# Rigid-QFN-1.net
KiCad netlist of a schematic drawn in Altium Designer
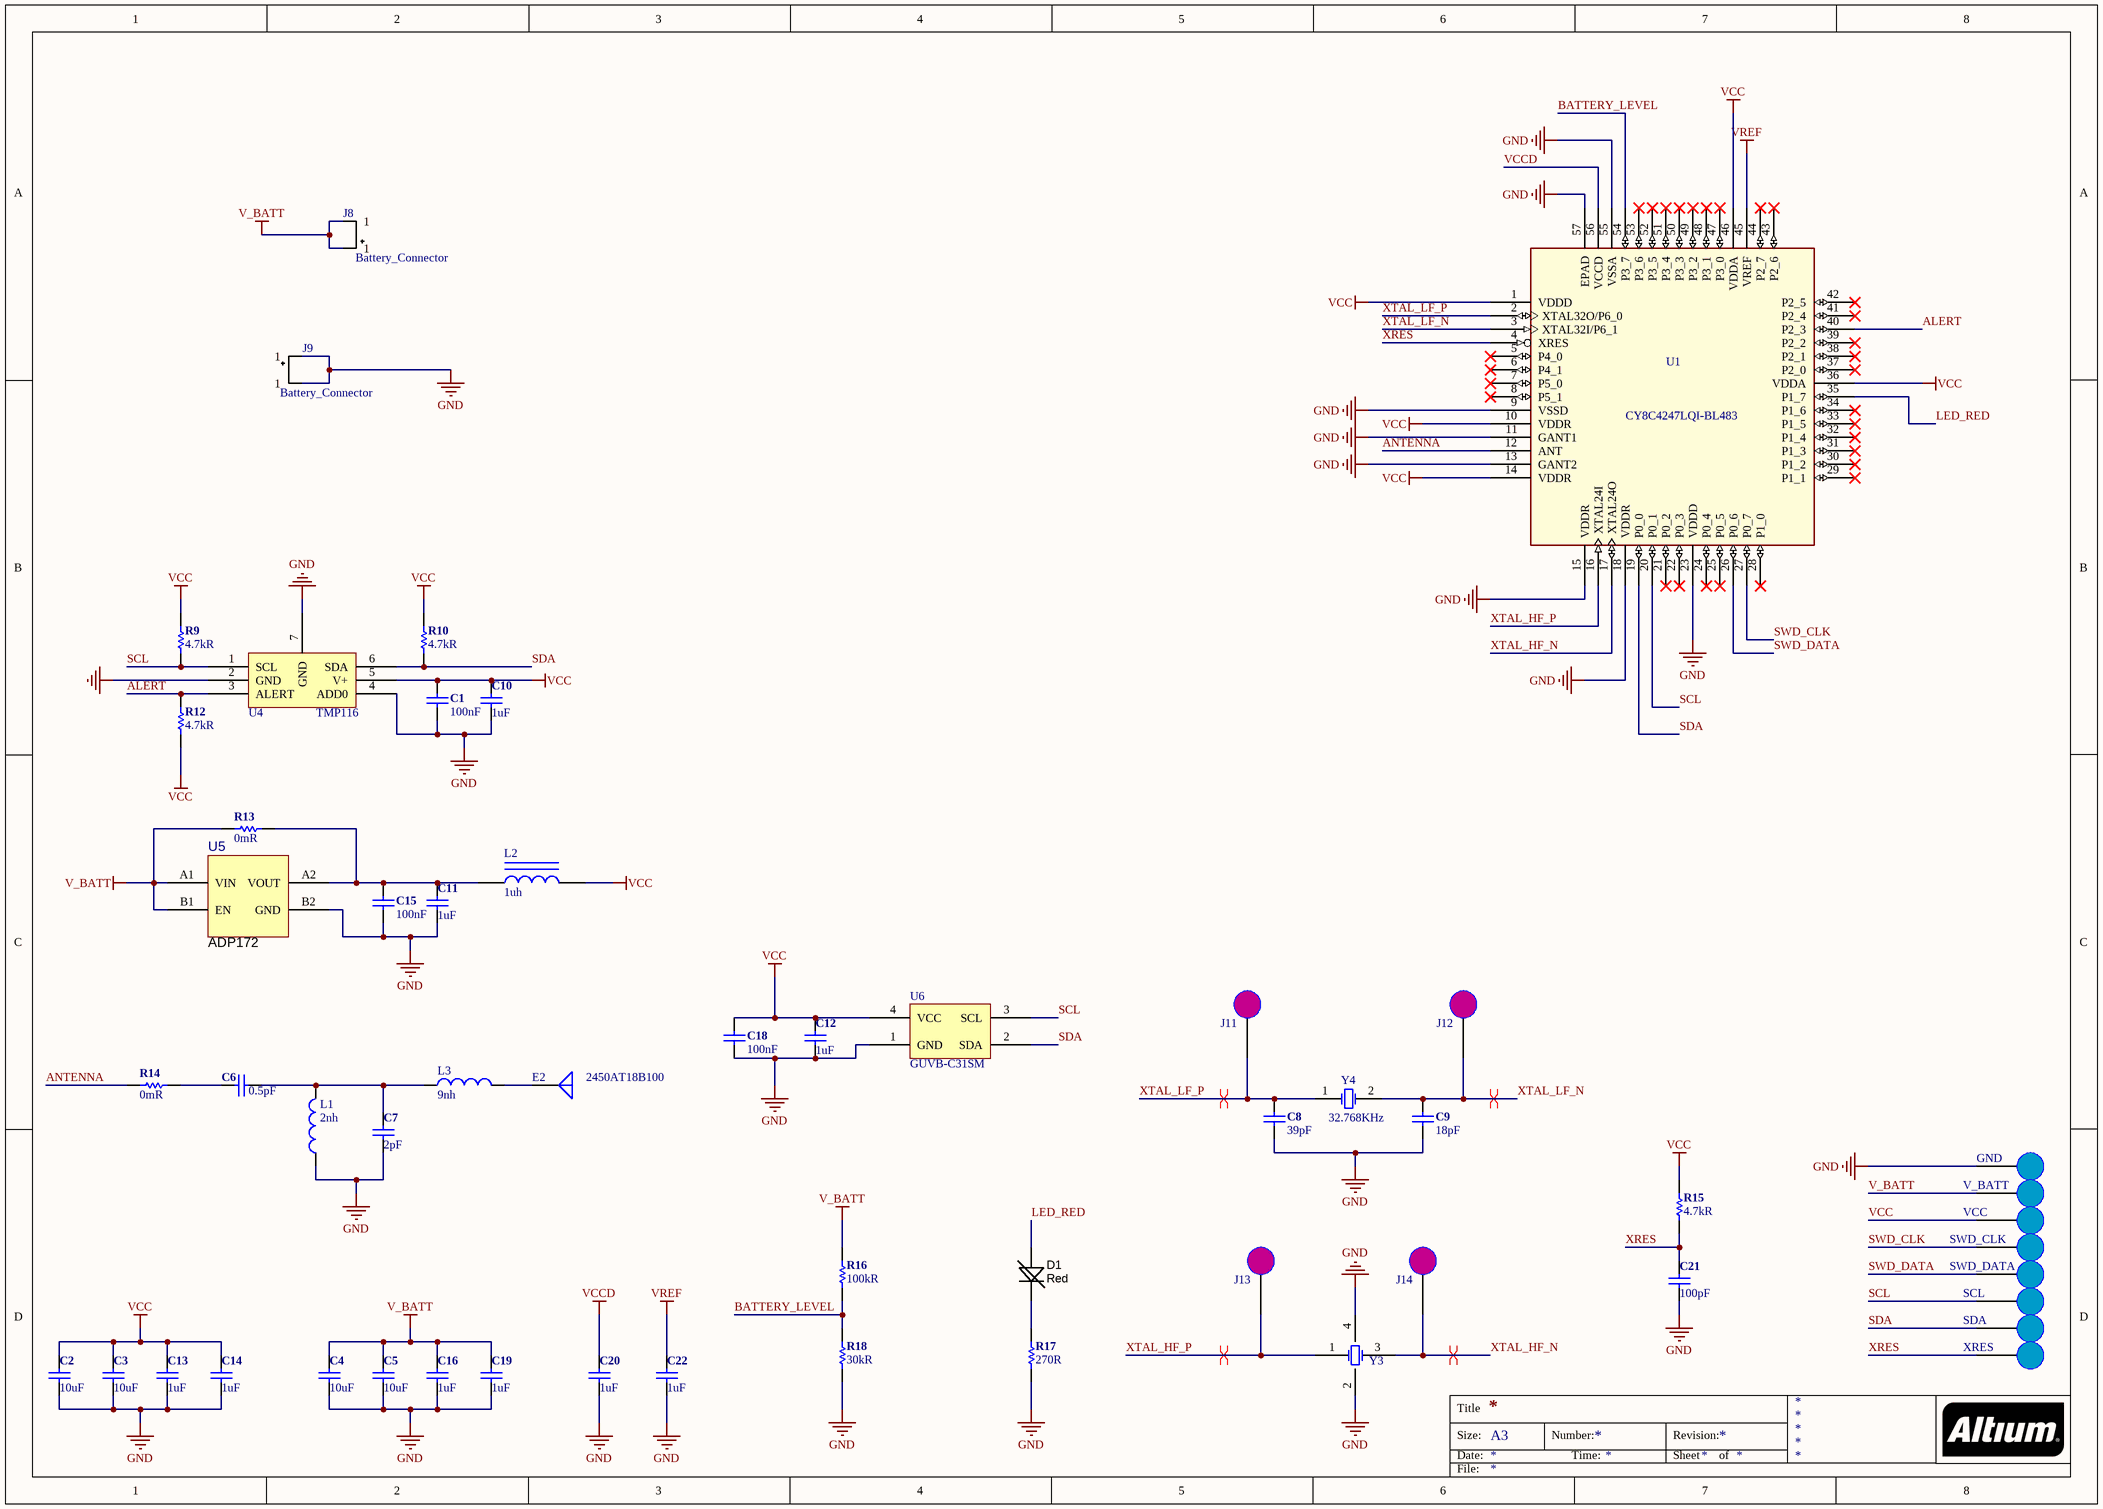
[diagram p0: Rigid-QFN-1.SchDoc]

(export (version "E")
  (design (tool "Eeschema 10.0.6"))
  (components
    (comp (ref "C1")
      (value "100nF")
      (footprint "CAP_0402(1005)_M")
      (description "___ OHM ___ mW 0402(1005) SMD")
      (fields
        (field (name "MANUFACTURER") "Yageo")
        (field (name "MANUFACTURER PART NUMBER") "CC0402ZRY5V6BB104")
      )
      (libsource (lib "tempsensor") (part "C-0402(1005)"))
    )
    (comp (ref "C2")
      (value "10uF")
      (footprint "CAP_0402(1005)_M")
      (description "___ OHM ___ mW 0402(1005) SMD")
      (fields
        (field (name "MANUFACTURER") "Murata")
        (field (name "MANUFACTURER PART NUMBER") "GRM155R60J106ME15D")
      )
      (libsource (lib "tempsensor") (part "C-0402(1005)"))
    )
    (comp (ref "C3")
      (value "10uF")
      (footprint "CAP_0402(1005)_M")
      (description "___ OHM ___ mW 0402(1005) SMD")
      (fields
        (field (name "MANUFACTURER") "Murata")
        (field (name "MANUFACTURER PART NUMBER") "GRM155R60J106ME15D")
      )
      (libsource (lib "tempsensor") (part "C-0402(1005)"))
    )
    (comp (ref "C4")
      (value "10uF")
      (footprint "CAP_0402(1005)_M")
      (description "___ OHM ___ mW 0402(1005) SMD")
      (fields
        (field (name "MANUFACTURER") "Murata")
        (field (name "MANUFACTURER PART NUMBER") "GRM155R60J106ME15D")
      )
      (libsource (lib "tempsensor") (part "C-0402(1005)"))
    )
    (comp (ref "C5")
      (value "10uF")
      (footprint "CAP_0402(1005)_M")
      (description "___ OHM ___ mW 0402(1005) SMD")
      (fields
        (field (name "MANUFACTURER") "Murata")
        (field (name "MANUFACTURER PART NUMBER") "GRM155R60J106ME15D")
      )
      (libsource (lib "tempsensor") (part "C-0402(1005)"))
    )
    (comp (ref "C6")
      (value "0.5pF")
      (footprint "CAP_0402(1005)_M")
      (description "___ OHM ___ mW 0402(1005) SMD")
      (fields
        (field (name "MANUFACTURER") "Murata")
        (field (name "MANUFACTURER PART NUMBER") "GJM1555C1HR50WB01D")
      )
      (libsource (lib "tempsensor") (part "C-0402(1005)"))
    )
    (comp (ref "C7")
      (value "2pF")
      (footprint "CAP_0402(1005)_M")
      (description "___ OHM ___ mW 0402(1005) SMD")
      (fields
        (field (name "MANUFACTURER") "Murata")
        (field (name "MANUFACTURER PART NUMBER") "GJM1555C1H2R0BB01D")
      )
      (libsource (lib "tempsensor") (part "C-0402(1005)"))
    )
    (comp (ref "C8")
      (value "39pF")
      (footprint "CAP_0402(1005)_M")
      (description "___ OHM ___ mW 0402(1005) SMD")
      (fields
        (field (name "MANUFACTURER") "KEMET")
        (field (name "MANUFACTURER PART NUMBER") "CBR04C390F5GAC")
      )
      (libsource (lib "tempsensor") (part "C-0402(1005)"))
    )
    (comp (ref "C9")
      (value "18pF")
      (footprint "CAP_0402(1005)_M")
      (description "___ OHM ___ mW 0402(1005) SMD")
      (fields
        (field (name "MANUFACTURER") "Murata")
        (field (name "MANUFACTURER PART NUMBER") "GJM1555C1H180FB01D")
      )
      (libsource (lib "tempsensor") (part "C-0402(1005)"))
    )
    (comp (ref "C10")
      (value "1uF")
      (footprint "CAP_0402(1005)_M")
      (description "___ OHM ___ mW 0402(1005) SMD")
      (fields
        (field (name "MANUFACTURER") "KEMET")
        (field (name "MANUFACTURER PART NUMBER") "C0402C105K8PACTU")
      )
      (libsource (lib "tempsensor") (part "C-0402(1005)"))
    )
    (comp (ref "C11")
      (value "1uF")
      (footprint "CAP_0402(1005)_M")
      (description "___ OHM ___ mW 0402(1005) SMD")
      (fields
        (field (name "MANUFACTURER") "KEMET")
        (field (name "MANUFACTURER PART NUMBER") "C0402C105K8PACTU")
      )
      (libsource (lib "tempsensor") (part "C-0402(1005)"))
    )
    (comp (ref "C12")
      (value "1uF")
      (footprint "CAP_0402(1005)_M")
      (description "___ OHM ___ mW 0402(1005) SMD")
      (fields
        (field (name "MANUFACTURER") "KEMET")
        (field (name "MANUFACTURER PART NUMBER") "C0402C105K8PACTU")
      )
      (libsource (lib "tempsensor") (part "C-0402(1005)"))
    )
    (comp (ref "C13")
      (value "1uF")
      (footprint "CAP_0402(1005)_M")
      (description "___ OHM ___ mW 0402(1005) SMD")
      (fields
        (field (name "MANUFACTURER") "KEMET")
        (field (name "MANUFACTURER PART NUMBER") "C0402C105K8PACTU")
      )
      (libsource (lib "tempsensor") (part "C-0402(1005)"))
    )
    (comp (ref "C14")
      (value "1uF")
      (footprint "CAP_0402(1005)_M")
      (description "___ OHM ___ mW 0402(1005) SMD")
      (fields
        (field (name "MANUFACTURER") "KEMET")
        (field (name "MANUFACTURER PART NUMBER") "C0402C105K8PACTU")
      )
      (libsource (lib "tempsensor") (part "C-0402(1005)"))
    )
    (comp (ref "C15")
      (value "100nF")
      (footprint "CAP_0402(1005)_M")
      (description "___ OHM ___ mW 0402(1005) SMD")
      (fields
        (field (name "MANUFACTURER") "Yageo")
        (field (name "MANUFACTURER PART NUMBER") "CC0402ZRY5V6BB104")
      )
      (libsource (lib "tempsensor") (part "C-0402(1005)"))
    )
    (comp (ref "C16")
      (value "1uF")
      (footprint "CAP_0402(1005)_M")
      (description "___ OHM ___ mW 0402(1005) SMD")
      (fields
        (field (name "MANUFACTURER") "KEMET")
        (field (name "MANUFACTURER PART NUMBER") "C0402C105K8PACTU")
      )
      (libsource (lib "tempsensor") (part "C-0402(1005)"))
    )
    (comp (ref "C18")
      (value "100nF")
      (footprint "CAP_0402(1005)_M")
      (description "___ OHM ___ mW 0402(1005) SMD")
      (fields
        (field (name "MANUFACTURER") "Yageo")
        (field (name "MANUFACTURER PART NUMBER") "CC0402ZRY5V6BB104")
      )
      (libsource (lib "tempsensor") (part "C-0402(1005)"))
    )
    (comp (ref "C19")
      (value "1uF")
      (footprint "CAP_0402(1005)_M")
      (description "___ OHM ___ mW 0402(1005) SMD")
      (fields
        (field (name "MANUFACTURER") "KEMET")
        (field (name "MANUFACTURER PART NUMBER") "C0402C105K8PACTU")
      )
      (libsource (lib "tempsensor") (part "C-0402(1005)"))
    )
    (comp (ref "C20")
      (value "1uF")
      (footprint "CAP_0402(1005)_M")
      (description "___ OHM ___ mW 0402(1005) SMD")
      (fields
        (field (name "MANUFACTURER") "KEMET")
        (field (name "MANUFACTURER PART NUMBER") "C0402C105K8PACTU")
      )
      (libsource (lib "tempsensor") (part "C-0402(1005)"))
    )
    (comp (ref "C21")
      (value "100pF")
      (footprint "CAP_0402(1005)_M")
      (description "___ OHM ___ mW 0402(1005) SMD")
      (fields
        (field (name "MANUFACTURER") "Wurth Electronics")
        (field (name "MANUFACTURER PART NUMBER") "885012005013")
      )
      (libsource (lib "tempsensor") (part "C-0402(1005)"))
    )
    (comp (ref "C22")
      (value "1uF")
      (footprint "CAP_0402(1005)_M")
      (description "___ OHM ___ mW 0402(1005) SMD")
      (fields
        (field (name "MANUFACTURER") "KEMET")
        (field (name "MANUFACTURER PART NUMBER") "C0402C105K8PACTU")
      )
      (libsource (lib "tempsensor") (part "C-0402(1005)"))
    )
    (comp (ref "D1")
      (value "Red")
      (footprint "LED_0402(1005)")
      (description "LED, 0402(1005) SMD")
      (fields
        (field (name "MANUFACTURER") "Kingbright")
        (field (name "MANUFACTURER PART NUMBER") "APHHS1005SURCK")
      )
      (libsource (lib "tempsensor") (part "LED_0402(1005)"))
    )
    (comp (ref "E2")
      (value "2450AT18B100")
      (footprint "2450AT18B100")
      (description "2.4 GHz BLE Antenna")
      (fields
        (field (name "MANUFACTURER") "Johanson")
        (field (name "MANUFACTURER PART NUMBER") "2450AT18B100E")
      )
      (libsource (lib "tempsensor") (part "2450AT18B100"))
    )
    (comp (ref "GND")
      (value "Probe-Pin Pad")
      (footprint "Pogo-Pin-Pad")
      (libsource (lib "tempsensor") (part "Probe-Pin Pad"))
    )
    (comp (ref "J8")
      (value "Battery_Connector")
      (footprint "Battery_PAD")
      (libsource (lib "tempsensor") (part "Battery_Connector"))
    )
    (comp (ref "J9")
      (value "Battery_Connector")
      (footprint "Battery_PAD")
      (libsource (lib "tempsensor") (part "Battery_Connector"))
    )
    (comp (ref "J11")
      (value "Probe-CLOCK")
      (footprint "Pogo-CLOCK-PAD")
      (libsource (lib "tempsensor") (part "Probe-CLOCK"))
    )
    (comp (ref "J12")
      (value "Probe-CLOCK")
      (footprint "Pogo-CLOCK-PAD")
      (libsource (lib "tempsensor") (part "Probe-CLOCK"))
    )
    (comp (ref "J13")
      (value "Probe-CLOCK")
      (footprint "Pogo-CLOCK-PAD")
      (libsource (lib "tempsensor") (part "Probe-CLOCK"))
    )
    (comp (ref "J14")
      (value "Probe-CLOCK")
      (footprint "Pogo-CLOCK-PAD")
      (libsource (lib "tempsensor") (part "Probe-CLOCK"))
    )
    (comp (ref "L1")
      (value "2nh")
      (footprint "IND_0402(1005)_M")
      (fields
        (field (name "MANUFACTURER") "Abracon")
        (field (name "MANUFACTURER PART NUMBER") "AISC-0402-2N0J-T")
        (field (name "TOLERANCE") "5%")
      )
      (libsource (lib "tempsensor") (part "I-0402(1005)"))
    )
    (comp (ref "L2")
      (value "1uh")
      (footprint "IND_0402(1005)_M")
      (description "Magnetic-Core Inductor")
      (fields
        (field (name "MANUFACTURER") "TDK")
        (field (name "MANUFACTURER PART NUMBER") "MLZ1005M1R0WT000")
      )
      (libsource (lib "tempsensor") (part "Inductor Iron"))
    )
    (comp (ref "L3")
      (value "9nh")
      (footprint "IND_0402(1005)_M")
      (fields
        (field (name "MANUFACTURER") "Murata")
        (field (name "MANUFACTURER PART NUMBER") "LQW15AN9N0G80D")
        (field (name "TOLERANCE") "2%")
      )
      (libsource (lib "tempsensor") (part "I-0402(1005)"))
    )
    (comp (ref "R9")
      (value "4.7kR")
      (footprint "RES_0402(1005)_M")
      (description "___ OHM ___ mW 0402(1005) SMD")
      (fields
        (field (name "MANUFACTURER") "Yageo")
        (field (name "MANUFACTURER PART NUMBER") "RC0402JR-074K7P")
      )
      (libsource (lib "tempsensor") (part "R-0402(1005)"))
    )
    (comp (ref "R10")
      (value "4.7kR")
      (footprint "RES_0402(1005)_M")
      (description "___ OHM ___ mW 0402(1005) SMD")
      (fields
        (field (name "MANUFACTURER") "Yageo")
        (field (name "MANUFACTURER PART NUMBER") "RC0402JR-074K7P")
      )
      (libsource (lib "tempsensor") (part "R-0402(1005)"))
    )
    (comp (ref "R12")
      (value "4.7kR")
      (footprint "RES_0402(1005)_M")
      (description "___ OHM ___ mW 0402(1005) SMD")
      (fields
        (field (name "MANUFACTURER") "Yageo")
        (field (name "MANUFACTURER PART NUMBER") "RC0402JR-074K7P")
      )
      (libsource (lib "tempsensor") (part "R-0402(1005)"))
    )
    (comp (ref "R13")
      (value "0mR")
      (footprint "RES_0402(1005)_M")
      (description "___ OHM ___ mW 0402(1005) SMD")
      (fields
        (field (name "MANUFACTURER") "Yageo")
        (field (name "MANUFACTURER PART NUMBER") "AC0402JR-070RL")
      )
      (libsource (lib "tempsensor") (part "R-0402(1005)"))
    )
    (comp (ref "R14")
      (value "0mR")
      (footprint "RES_0402(1005)_M")
      (description "___ OHM ___ mW 0402(1005) SMD")
      (fields
        (field (name "MANUFACTURER") "Yageo")
        (field (name "MANUFACTURER PART NUMBER") "AC0402JR-070RL")
      )
      (libsource (lib "tempsensor") (part "R-0402(1005)"))
    )
    (comp (ref "R15")
      (value "4.7kR")
      (footprint "RES_0402(1005)_M")
      (description "___ OHM ___ mW 0402(1005) SMD")
      (fields
        (field (name "MANUFACTURER") "Yageo")
        (field (name "MANUFACTURER PART NUMBER") "RC0402JR-074K7P")
      )
      (libsource (lib "tempsensor") (part "R-0402(1005)"))
    )
    (comp (ref "R16")
      (value "100kR")
      (footprint "RES_0402(1005)_M")
      (description "___ OHM ___ mW 0402(1005) SMD")
      (fields
        (field (name "MANUFACTURER") "Yageo")
        (field (name "MANUFACTURER PART NUMBER") "AC0402JR-07100KL")
      )
      (libsource (lib "tempsensor") (part "R-0402(1005)"))
    )
    (comp (ref "R17")
      (value "270R")
      (footprint "RES_0402(1005)_M")
      (description "___ OHM ___ mW 0402(1005) SMD")
      (fields
        (field (name "MANUFACTURER") "Yageo")
        (field (name "MANUFACTURER PART NUMBER") "RC0402JR-07270RL")
      )
      (libsource (lib "tempsensor") (part "R-0402(1005)"))
    )
    (comp (ref "R18")
      (value "30kR")
      (footprint "RES_0402(1005)_M")
      (description "___ OHM ___ mW 0402(1005) SMD")
      (fields
        (field (name "MANUFACTURER") "Yageo")
        (field (name "MANUFACTURER PART NUMBER") "RC0402JR-0730KL")
      )
      (libsource (lib "tempsensor") (part "R-0402(1005)"))
    )
    (comp (ref "SCL")
      (value "Probe-Pin Pad")
      (footprint "Pogo-Pin-Pad")
      (libsource (lib "tempsensor") (part "Probe-Pin Pad"))
    )
    (comp (ref "SDA")
      (value "Probe-Pin Pad")
      (footprint "Pogo-Pin-Pad")
      (libsource (lib "tempsensor") (part "Probe-Pin Pad"))
    )
    (comp (ref "SWD_CLK")
      (value "Probe-Pin Pad")
      (footprint "Pogo-Pin-Pad")
      (libsource (lib "tempsensor") (part "Probe-Pin Pad"))
    )
    (comp (ref "SWD_DATA")
      (value "Probe-Pin Pad")
      (footprint "Pogo-Pin-Pad")
      (libsource (lib "tempsensor") (part "Probe-Pin Pad"))
    )
    (comp (ref "U1")
      (value "CY8C4247LQI-BL483")
      (footprint "QFN40P700X700X60-57N")
      (fields (field (name "MANUFACTURER") "Cypress"))
      (libsource (lib "tempsensor") (part "CY8C4247LQI-BL483"))
    )
    (comp (ref "U4")
      (value "TMP116")
      (footprint "WSON-6")
      (description "TI Digital I2C Temperature Sensor")
      (fields
        (field (name "MANUFACTURER") "Texas Instruments")
        (field (name "MANUFACTURER PART NUMBER") "TMP116AIDRVT")
      )
      (libsource (lib "tempsensor") (part "TMP116"))
    )
    (comp (ref "U5")
      (value "ADP172")
      (footprint "ADP172")
      (description "3V LDO")
      (fields
        (field (name "MANUFACTURER") "Analog Devices")
        (field (name "MANUFACTURER PART NUMBER") "ADP172ACBZ-3.0-R7")
      )
      (libsource (lib "tempsensor") (part "ADP172"))
    )
    (comp (ref "U6")
      (value "GUVB-C31SM")
      (footprint "GUVB-C31SM")
      (libsource (lib "tempsensor") (part "GUVB-C31SM"))
    )
    (comp (ref "VCC")
      (value "Probe-Pin Pad")
      (footprint "Pogo-Pin-Pad")
      (libsource (lib "tempsensor") (part "Probe-Pin Pad"))
    )
    (comp (ref "V_BATT")
      (value "Probe-Pin Pad")
      (footprint "Pogo-Pin-Pad")
      (libsource (lib "tempsensor") (part "Probe-Pin Pad"))
    )
    (comp (ref "XRES")
      (value "Probe-Pin Pad")
      (footprint "Pogo-Pin-Pad")
      (libsource (lib "tempsensor") (part "Probe-Pin Pad"))
    )
    (comp (ref "Y3")
      (value "ECX-2236")
      (footprint "ECX-2236")
      (description "24 MHz Crystal")
      (fields
        (field (name "MANUFACTURER") "ECS International")
        (field (name "MANUFACTURER PART NUMBER") "ECS-240-8-36CKM-TR")
      )
      (libsource (lib "tempsensor") (part "ECX-2236"))
    )
    (comp (ref "Y4")
      (value "32.768KHz")
      (footprint "ABS05")
      (description "Crystal Oscillator")
      (fields
        (field (name "MANUFACTURER") "Abracon")
        (field (name "MANUFACTURER PART NUMBER") "ABS05-32.768KHZ-T")
      )
      (libsource (lib "tempsensor") (part "ABS05"))
    )
  )
  (nets
    (net (code "1") (name "/ALERT") (class "Default")
      (node (ref "R12") (pin "2") (pinfunction "2_2") (pintype "passive"))
      (node (ref "U1") (pin "40") (pinfunction "P2_3_40") (pintype "bidirectional"))
      (node (ref "U4") (pin "3") (pinfunction "ALERT_3") (pintype "passive"))
    )
    (net (code "2") (name "/ANTENNA") (class "Default")
      (node (ref "R14") (pin "1") (pinfunction "1_1") (pintype "passive"))
      (node (ref "U1") (pin "12") (pinfunction "ANT_12") (pintype "passive"))
    )
    (net (code "3") (name "/BATTERY_LEVEL") (class "Default")
      (node (ref "R16") (pin "2") (pinfunction "2_2") (pintype "passive"))
      (node (ref "R18") (pin "1") (pinfunction "1_1") (pintype "passive"))
      (node (ref "U1") (pin "54") (pinfunction "P3_7_54") (pintype "bidirectional"))
    )
    (net (code "4") (name "/LED_RED") (class "Default")
      (node (ref "D1") (pin "A") (pinfunction "A_A") (pintype "passive"))
      (node (ref "U1") (pin "35") (pinfunction "P1_7_35") (pintype "bidirectional"))
    )
    (net (code "5") (name "/SCL") (class "Default")
      (node (ref "R9") (pin "1") (pinfunction "1_1") (pintype "passive"))
      (node (ref "SCL") (pin "1") (pinfunction "1_1") (pintype "passive"))
      (node (ref "U1") (pin "20") (pinfunction "P0_1_20") (pintype "bidirectional"))
      (node (ref "U4") (pin "1") (pinfunction "SCL_1") (pintype "passive"))
      (node (ref "U6") (pin "3") (pinfunction "SCL_3") (pintype "passive"))
    )
    (net (code "6") (name "/SDA") (class "Default")
      (node (ref "R10") (pin "1") (pinfunction "1_1") (pintype "passive"))
      (node (ref "SDA") (pin "1") (pinfunction "1_1") (pintype "passive"))
      (node (ref "U1") (pin "19") (pinfunction "P0_0_19") (pintype "bidirectional"))
      (node (ref "U4") (pin "6") (pinfunction "SDA_6") (pintype "passive"))
      (node (ref "U6") (pin "2") (pinfunction "SDA_2") (pintype "passive"))
    )
    (net (code "7") (name "/SWD_CLK") (class "Default")
      (node (ref "SWD_CLK") (pin "1") (pinfunction "1_1") (pintype "passive"))
      (node (ref "U1") (pin "27") (pinfunction "P0_7_27") (pintype "bidirectional"))
    )
    (net (code "8") (name "/SWD_DATA") (class "Default")
      (node (ref "SWD_DATA") (pin "1") (pinfunction "1_1") (pintype "passive"))
      (node (ref "U1") (pin "26") (pinfunction "P0_6_26") (pintype "bidirectional"))
    )
    (net (code "9") (name "/XRES") (class "Default")
      (node (ref "C21") (pin "1") (pinfunction "1_1") (pintype "passive"))
      (node (ref "R15") (pin "2") (pinfunction "2_2") (pintype "passive"))
      (node (ref "U1") (pin "4") (pinfunction "XRES_4") (pintype "input"))
      (node (ref "XRES") (pin "1") (pinfunction "1_1") (pintype "passive"))
    )
    (net (code "10") (name "/XTAL_HF_N") (class "Default")
      (node (ref "J14") (pin "1") (pinfunction "1_1") (pintype "passive"))
      (node (ref "U1") (pin "17") (pinfunction "XTAL24O_17") (pintype "bidirectional"))
      (node (ref "Y3") (pin "3") (pinfunction "OSC2_3") (pintype "passive"))
    )
    (net (code "11") (name "/XTAL_HF_P") (class "Default")
      (node (ref "J13") (pin "1") (pinfunction "1_1") (pintype "passive"))
      (node (ref "U1") (pin "16") (pinfunction "XTAL24I_16") (pintype "input"))
      (node (ref "Y3") (pin "1") (pinfunction "OSC1_1") (pintype "passive"))
    )
    (net (code "12") (name "/XTAL_LF_N") (class "Default")
      (node (ref "C9") (pin "1") (pinfunction "1_1") (pintype "passive"))
      (node (ref "J12") (pin "1") (pinfunction "1_1") (pintype "passive"))
      (node (ref "U1") (pin "3") (pinfunction "XTAL32I/P6_1_3") (pintype "input"))
      (node (ref "Y4") (pin "2") (pinfunction "OSC2_2") (pintype "passive"))
    )
    (net (code "13") (name "/XTAL_LF_P") (class "Default")
      (node (ref "C8") (pin "1") (pinfunction "1_1") (pintype "passive"))
      (node (ref "J11") (pin "1") (pinfunction "1_1") (pintype "passive"))
      (node (ref "U1") (pin "2") (pinfunction "XTAL32O/P6_0_2") (pintype "bidirectional"))
      (node (ref "Y4") (pin "1") (pinfunction "OSC1_1") (pintype "passive"))
    )
    (net (code "14") (name "GND") (class "Default")
      (node (ref "C1") (pin "2") (pinfunction "2_2") (pintype "passive"))
      (node (ref "C10") (pin "2") (pinfunction "2_2") (pintype "passive"))
      (node (ref "C11") (pin "2") (pinfunction "2_2") (pintype "passive"))
      (node (ref "C12") (pin "2") (pinfunction "2_2") (pintype "passive"))
      (node (ref "C13") (pin "2") (pinfunction "2_2") (pintype "passive"))
      (node (ref "C14") (pin "2") (pinfunction "2_2") (pintype "passive"))
      (node (ref "C15") (pin "2") (pinfunction "2_2") (pintype "passive"))
      (node (ref "C16") (pin "2") (pinfunction "2_2") (pintype "passive"))
      (node (ref "C18") (pin "2") (pinfunction "2_2") (pintype "passive"))
      (node (ref "C19") (pin "2") (pinfunction "2_2") (pintype "passive"))
      (node (ref "C2") (pin "2") (pinfunction "2_2") (pintype "passive"))
      (node (ref "C20") (pin "2") (pinfunction "2_2") (pintype "passive"))
      (node (ref "C21") (pin "2") (pinfunction "2_2") (pintype "passive"))
      (node (ref "C22") (pin "2") (pinfunction "2_2") (pintype "passive"))
      (node (ref "C3") (pin "2") (pinfunction "2_2") (pintype "passive"))
      (node (ref "C4") (pin "2") (pinfunction "2_2") (pintype "passive"))
      (node (ref "C5") (pin "2") (pinfunction "2_2") (pintype "passive"))
      (node (ref "C7") (pin "2") (pinfunction "2_2") (pintype "passive"))
      (node (ref "C8") (pin "2") (pinfunction "2_2") (pintype "passive"))
      (node (ref "C9") (pin "2") (pinfunction "2_2") (pintype "passive"))
      (node (ref "GND") (pin "1") (pinfunction "1_1") (pintype "passive"))
      (node (ref "J9") (pin "1") (pinfunction "1_1") (pintype "passive"))
      (node (ref "L1") (pin "1") (pinfunction "1_1") (pintype "passive"))
      (node (ref "R17") (pin "2") (pinfunction "2_2") (pintype "passive"))
      (node (ref "R18") (pin "2") (pinfunction "2_2") (pintype "passive"))
      (node (ref "U1") (pin "11") (pinfunction "GANT1_11") (pintype "power_in"))
      (node (ref "U1") (pin "13") (pinfunction "GANT2_13") (pintype "power_in"))
      (node (ref "U1") (pin "15") (pinfunction "VDDR_15") (pintype "power_in"))
      (node (ref "U1") (pin "18") (pinfunction "VDDR_18") (pintype "power_in"))
      (node (ref "U1") (pin "23") (pinfunction "VDDD_23") (pintype "power_in"))
      (node (ref "U1") (pin "55") (pinfunction "VSSA_55") (pintype "power_in"))
      (node (ref "U1") (pin "57") (pinfunction "EPAD_57") (pintype "power_in"))
      (node (ref "U1") (pin "9") (pinfunction "VSSD_9") (pintype "power_in"))
      (node (ref "U4") (pin "2") (pinfunction "GND_2") (pintype "passive"))
      (node (ref "U4") (pin "4") (pinfunction "ADD0_4") (pintype "passive"))
      (node (ref "U4") (pin "7") (pinfunction "GND_7") (pintype "passive"))
      (node (ref "U5") (pin "B2") (pinfunction "GND_B2") (pintype "passive"))
      (node (ref "U6") (pin "1") (pinfunction "GND_1") (pintype "passive"))
      (node (ref "Y3") (pin "2") (pinfunction "GND_2") (pintype "passive"))
      (node (ref "Y3") (pin "4") (pinfunction "GND_4") (pintype "passive"))
    )
    (net (code "15") (name "Net-(C6-Pad1)") (class "Default")
      (node (ref "C6") (pin "1") (pinfunction "1_1") (pintype "passive"))
      (node (ref "R14") (pin "2") (pinfunction "2_2") (pintype "passive"))
    )
    (net (code "16") (name "Net-(C6-Pad2)") (class "Default")
      (node (ref "C6") (pin "2") (pinfunction "2_2") (pintype "passive"))
      (node (ref "C7") (pin "1") (pinfunction "1_1") (pintype "passive"))
      (node (ref "L1") (pin "2") (pinfunction "2_2") (pintype "passive"))
      (node (ref "L3") (pin "1") (pinfunction "1_1") (pintype "passive"))
    )
    (net (code "17") (name "Net-(D1-PadK)") (class "Default")
      (node (ref "D1") (pin "K") (pinfunction "K_K") (pintype "passive"))
      (node (ref "R17") (pin "1") (pinfunction "1_1") (pintype "passive"))
    )
    (net (code "18") (name "Net-(E2-A)") (class "Default")
      (node (ref "E2") (pin "1") (pinfunction "A_1") (pintype "passive"))
      (node (ref "L3") (pin "2") (pinfunction "2_2") (pintype "passive"))
    )
    (net (code "19") (name "Net-(U5-VOUT)") (class "Default")
      (node (ref "C11") (pin "1") (pinfunction "1_1") (pintype "passive"))
      (node (ref "C15") (pin "1") (pinfunction "1_1") (pintype "passive"))
      (node (ref "L2") (pin "1") (pinfunction "1_1") (pintype "passive"))
      (node (ref "R13") (pin "2") (pinfunction "2_2") (pintype "passive"))
      (node (ref "U5") (pin "A2") (pinfunction "VOUT_A2") (pintype "passive"))
    )
    (net (code "20") (name "VCC") (class "Default")
      (node (ref "C1") (pin "1") (pinfunction "1_1") (pintype "passive"))
      (node (ref "C10") (pin "1") (pinfunction "1_1") (pintype "passive"))
      (node (ref "C12") (pin "1") (pinfunction "1_1") (pintype "passive"))
      (node (ref "C13") (pin "1") (pinfunction "1_1") (pintype "passive"))
      (node (ref "C14") (pin "1") (pinfunction "1_1") (pintype "passive"))
      (node (ref "C18") (pin "1") (pinfunction "1_1") (pintype "passive"))
      (node (ref "C2") (pin "1") (pinfunction "1_1") (pintype "passive"))
      (node (ref "C3") (pin "1") (pinfunction "1_1") (pintype "passive"))
      (node (ref "L2") (pin "2") (pinfunction "2_2") (pintype "passive"))
      (node (ref "R10") (pin "2") (pinfunction "2_2") (pintype "passive"))
      (node (ref "R12") (pin "1") (pinfunction "1_1") (pintype "passive"))
      (node (ref "R15") (pin "1") (pinfunction "1_1") (pintype "passive"))
      (node (ref "R9") (pin "2") (pinfunction "2_2") (pintype "passive"))
      (node (ref "U1") (pin "1") (pinfunction "VDDD_1") (pintype "power_in"))
      (node (ref "U1") (pin "10") (pinfunction "VDDR_10") (pintype "power_in"))
      (node (ref "U1") (pin "14") (pinfunction "VDDR_14") (pintype "power_in"))
      (node (ref "U1") (pin "36") (pinfunction "VDDA_36") (pintype "power_in"))
      (node (ref "U1") (pin "46") (pinfunction "VDDA_46") (pintype "power_in"))
      (node (ref "U4") (pin "5") (pinfunction "V+_5") (pintype "passive"))
      (node (ref "U6") (pin "4") (pinfunction "VCC_4") (pintype "passive"))
      (node (ref "VCC") (pin "1") (pinfunction "1_1") (pintype "passive"))
    )
    (net (code "21") (name "VCCD") (class "Default")
      (node (ref "C20") (pin "1") (pinfunction "1_1") (pintype "passive"))
      (node (ref "U1") (pin "56") (pinfunction "VCCD_56") (pintype "power_in"))
    )
    (net (code "22") (name "VREF") (class "Default")
      (node (ref "C22") (pin "1") (pinfunction "1_1") (pintype "passive"))
      (node (ref "U1") (pin "45") (pinfunction "VREF_45") (pintype "power_in"))
    )
    (net (code "23") (name "V_BATT") (class "Default")
      (node (ref "C16") (pin "1") (pinfunction "1_1") (pintype "passive"))
      (node (ref "C19") (pin "1") (pinfunction "1_1") (pintype "passive"))
      (node (ref "C4") (pin "1") (pinfunction "1_1") (pintype "passive"))
      (node (ref "C5") (pin "1") (pinfunction "1_1") (pintype "passive"))
      (node (ref "J8") (pin "1") (pinfunction "1_1") (pintype "passive"))
      (node (ref "R13") (pin "1") (pinfunction "1_1") (pintype "passive"))
      (node (ref "R16") (pin "1") (pinfunction "1_1") (pintype "passive"))
      (node (ref "U5") (pin "A1") (pinfunction "VIN_A1") (pintype "passive"))
      (node (ref "U5") (pin "B1") (pinfunction "EN_B1") (pintype "passive"))
      (node (ref "V_BATT") (pin "1") (pinfunction "1_1") (pintype "passive"))
    )
    (net (code "24") (name "unconnected-(U1-P0_2-Pad21)") (class "Default")
      (node (ref "U1") (pin "21") (pinfunction "P0_2_21") (pintype "bidirectional+no_connect"))
    )
    (net (code "25") (name "unconnected-(U1-P0_3-Pad22)") (class "Default")
      (node (ref "U1") (pin "22") (pinfunction "P0_3_22") (pintype "bidirectional+no_connect"))
    )
    (net (code "26") (name "unconnected-(U1-P0_4-Pad24)") (class "Default")
      (node (ref "U1") (pin "24") (pinfunction "P0_4_24") (pintype "bidirectional+no_connect"))
    )
    (net (code "27") (name "unconnected-(U1-P0_5-Pad25)") (class "Default")
      (node (ref "U1") (pin "25") (pinfunction "P0_5_25") (pintype "bidirectional+no_connect"))
    )
    (net (code "28") (name "unconnected-(U1-P1_0-Pad28)") (class "Default")
      (node (ref "U1") (pin "28") (pinfunction "P1_0_28") (pintype "bidirectional+no_connect"))
    )
    (net (code "29") (name "unconnected-(U1-P1_1-Pad29)") (class "Default")
      (node (ref "U1") (pin "29") (pinfunction "P1_1_29") (pintype "bidirectional+no_connect"))
    )
    (net (code "30") (name "unconnected-(U1-P1_2-Pad30)") (class "Default")
      (node (ref "U1") (pin "30") (pinfunction "P1_2_30") (pintype "bidirectional+no_connect"))
    )
    (net (code "31") (name "unconnected-(U1-P1_3-Pad31)") (class "Default")
      (node (ref "U1") (pin "31") (pinfunction "P1_3_31") (pintype "bidirectional+no_connect"))
    )
    (net (code "32") (name "unconnected-(U1-P1_4-Pad32)") (class "Default")
      (node (ref "U1") (pin "32") (pinfunction "P1_4_32") (pintype "bidirectional+no_connect"))
    )
    (net (code "33") (name "unconnected-(U1-P1_5-Pad33)") (class "Default")
      (node (ref "U1") (pin "33") (pinfunction "P1_5_33") (pintype "bidirectional+no_connect"))
    )
    (net (code "34") (name "unconnected-(U1-P1_6-Pad34)") (class "Default")
      (node (ref "U1") (pin "34") (pinfunction "P1_6_34") (pintype "bidirectional+no_connect"))
    )
    (net (code "35") (name "unconnected-(U1-P2_0-Pad37)") (class "Default")
      (node (ref "U1") (pin "37") (pinfunction "P2_0_37") (pintype "bidirectional+no_connect"))
    )
    (net (code "36") (name "unconnected-(U1-P2_1-Pad38)") (class "Default")
      (node (ref "U1") (pin "38") (pinfunction "P2_1_38") (pintype "bidirectional+no_connect"))
    )
    (net (code "37") (name "unconnected-(U1-P2_2-Pad39)") (class "Default")
      (node (ref "U1") (pin "39") (pinfunction "P2_2_39") (pintype "bidirectional+no_connect"))
    )
    (net (code "38") (name "unconnected-(U1-P2_4-Pad41)") (class "Default")
      (node (ref "U1") (pin "41") (pinfunction "P2_4_41") (pintype "bidirectional+no_connect"))
    )
    (net (code "39") (name "unconnected-(U1-P2_5-Pad42)") (class "Default")
      (node (ref "U1") (pin "42") (pinfunction "P2_5_42") (pintype "bidirectional+no_connect"))
    )
    (net (code "40") (name "unconnected-(U1-P2_6-Pad43)") (class "Default")
      (node (ref "U1") (pin "43") (pinfunction "P2_6_43") (pintype "bidirectional+no_connect"))
    )
    (net (code "41") (name "unconnected-(U1-P2_7-Pad44)") (class "Default")
      (node (ref "U1") (pin "44") (pinfunction "P2_7_44") (pintype "bidirectional+no_connect"))
    )
    (net (code "42") (name "unconnected-(U1-P3_0-Pad47)") (class "Default")
      (node (ref "U1") (pin "47") (pinfunction "P3_0_47") (pintype "bidirectional+no_connect"))
    )
    (net (code "43") (name "unconnected-(U1-P3_1-Pad48)") (class "Default")
      (node (ref "U1") (pin "48") (pinfunction "P3_1_48") (pintype "bidirectional+no_connect"))
    )
    (net (code "44") (name "unconnected-(U1-P3_2-Pad49)") (class "Default")
      (node (ref "U1") (pin "49") (pinfunction "P3_2_49") (pintype "bidirectional+no_connect"))
    )
    (net (code "45") (name "unconnected-(U1-P3_3-Pad50)") (class "Default")
      (node (ref "U1") (pin "50") (pinfunction "P3_3_50") (pintype "bidirectional+no_connect"))
    )
    (net (code "46") (name "unconnected-(U1-P3_4-Pad51)") (class "Default")
      (node (ref "U1") (pin "51") (pinfunction "P3_4_51") (pintype "bidirectional+no_connect"))
    )
    (net (code "47") (name "unconnected-(U1-P3_5-Pad52)") (class "Default")
      (node (ref "U1") (pin "52") (pinfunction "P3_5_52") (pintype "bidirectional+no_connect"))
    )
    (net (code "48") (name "unconnected-(U1-P3_6-Pad53)") (class "Default")
      (node (ref "U1") (pin "53") (pinfunction "P3_6_53") (pintype "bidirectional+no_connect"))
    )
    (net (code "49") (name "unconnected-(U1-P4_0-Pad5)") (class "Default")
      (node (ref "U1") (pin "5") (pinfunction "P4_0_5") (pintype "bidirectional+no_connect"))
    )
    (net (code "50") (name "unconnected-(U1-P4_1-Pad6)") (class "Default")
      (node (ref "U1") (pin "6") (pinfunction "P4_1_6") (pintype "bidirectional+no_connect"))
    )
    (net (code "51") (name "unconnected-(U1-P5_0-Pad7)") (class "Default")
      (node (ref "U1") (pin "7") (pinfunction "P5_0_7") (pintype "bidirectional+no_connect"))
    )
    (net (code "52") (name "unconnected-(U1-P5_1-Pad8)") (class "Default")
      (node (ref "U1") (pin "8") (pinfunction "P5_1_8") (pintype "bidirectional+no_connect"))
    )
  )
)
